# floppy_IDC_to_SMT_rev_A.net
KiCad netlist of a schematic drawn in EAGLE
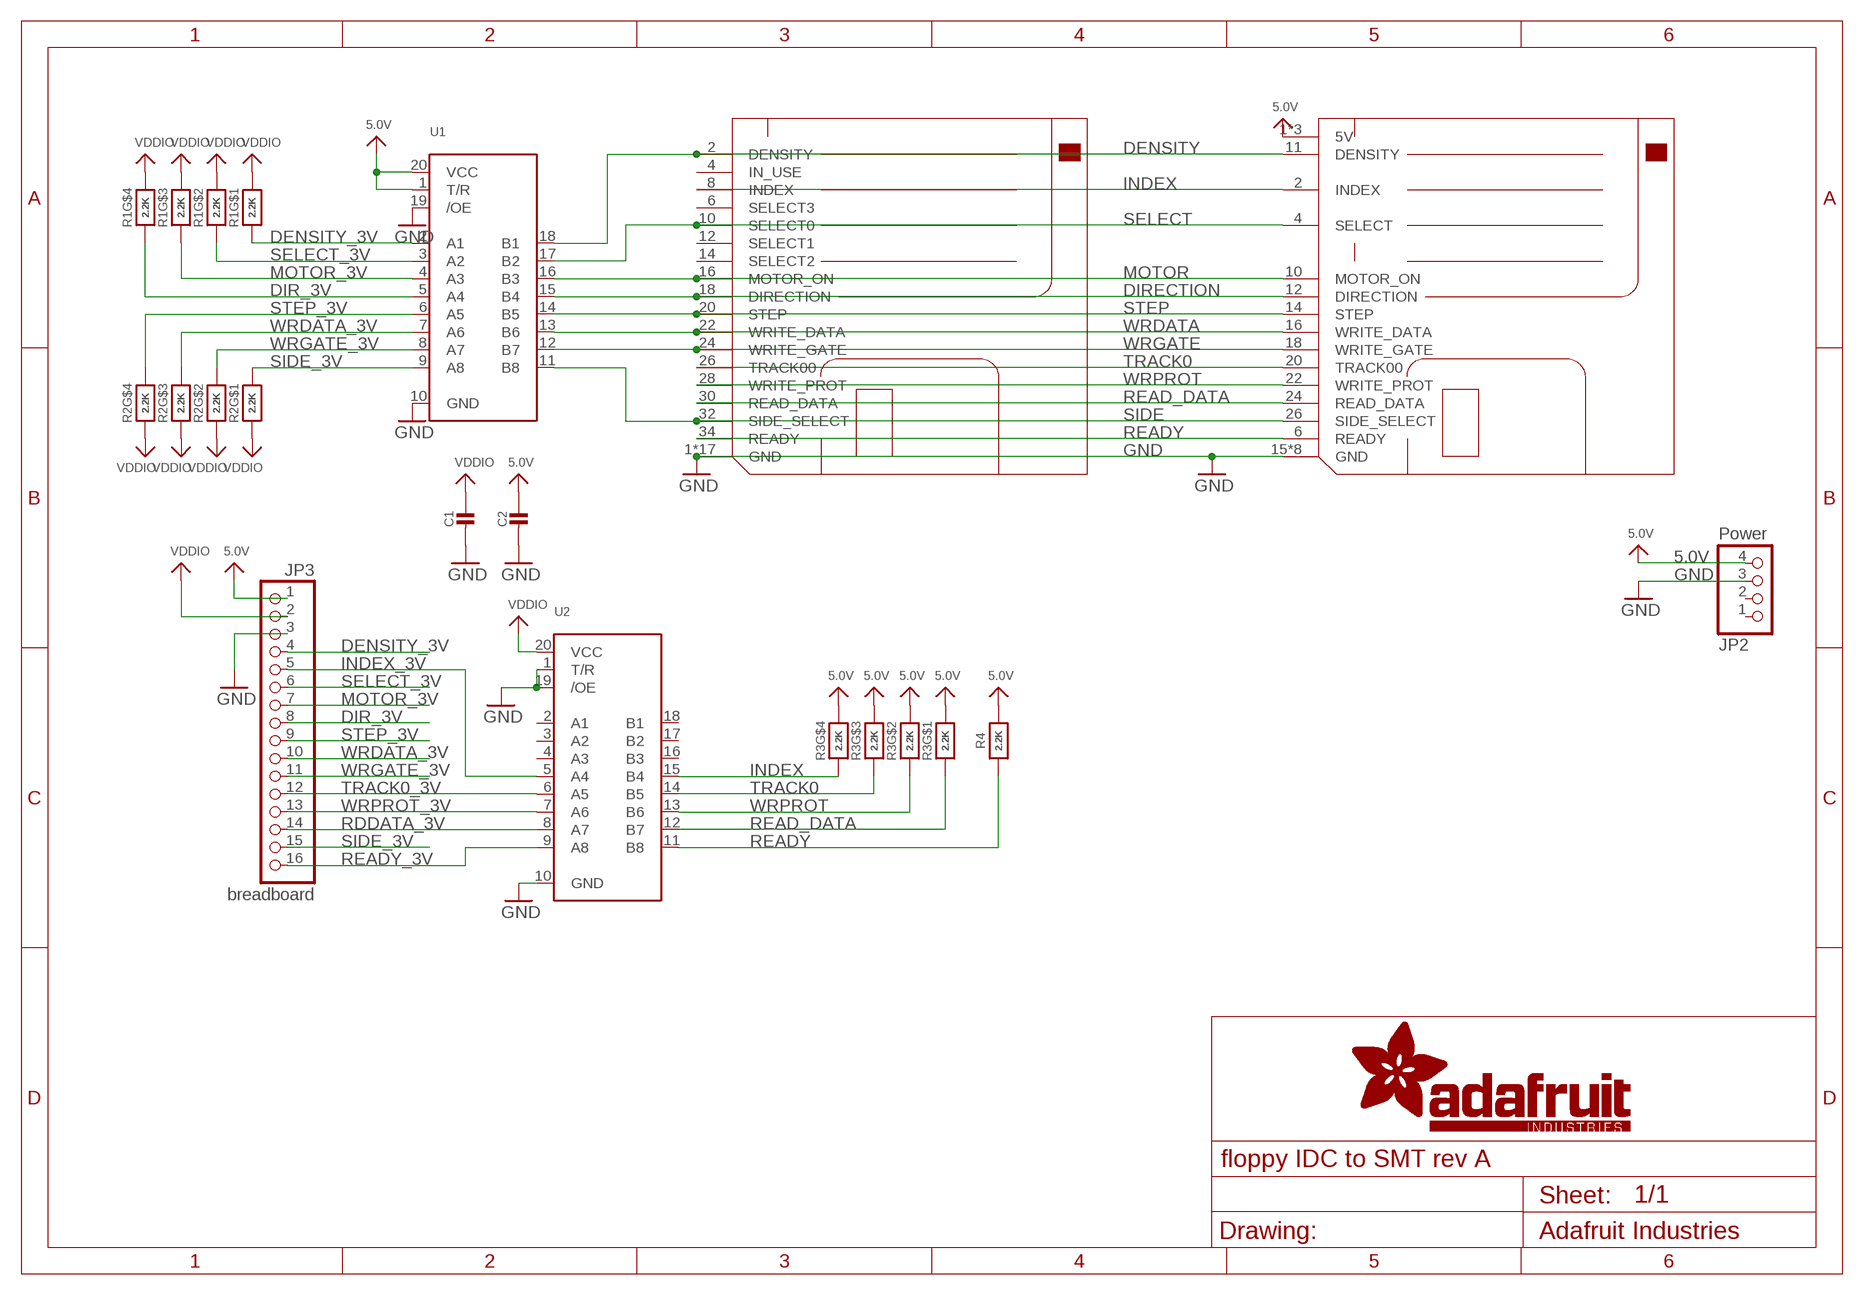
[diagram p0: schematic, sheet 1]

(export (version "E")
  (design (tool "Eeschema 10.0.6"))
  (components
    (comp (ref "C1")
      (value "CAP_CERAMIC0805-NOOUTLINE")
      (footprint "eagle-import:0805-NO")
      (libsource (lib "eagle-import") (part "CAP_CERAMIC0805-NOOUTLINE"))
    )
    (comp (ref "C2")
      (value "CAP_CERAMIC0805-NOOUTLINE")
      (footprint "eagle-import:0805-NO")
      (libsource (lib "eagle-import") (part "CAP_CERAMIC0805-NOOUTLINE"))
    )
    (comp (ref "FDD1")
      (value "FLOPPY_IDC_SHROUDED")
      (footprint "eagle-import:2X17_FLOPPY_IDC")
      (libsource (lib "eagle-import") (part "FLOPPY_IDC_SHROUDED"))
    )
    (comp (ref "FDD2")
      (value "FLOPPY_FPC")
      (footprint "eagle-import:FPC_26P_1MM")
      (libsource (lib "eagle-import") (part "FLOPPY_FPC"))
    )
    (comp (ref "JP2")
      (value "Power")
      (footprint "eagle-import:1X04_90")
      (libsource (lib "eagle-import") (part "PINHD-1X4/90"))
    )
    (comp (ref "JP3")
      (value "breadboard")
      (footprint "eagle-import:1X16")
      (libsource (lib "eagle-import") (part "PINHD-1X16"))
    )
    (comp (ref "R1")
      (value "2.2K")
      (footprint "eagle-import:RESPACK_4X0603")
      (libsource (lib "eagle-import") (part "RESISTOR_4PACK"))
    )
    (comp (ref "R2")
      (value "2.2K")
      (footprint "eagle-import:RESPACK_4X0603")
      (libsource (lib "eagle-import") (part "RESISTOR_4PACK"))
    )
    (comp (ref "R3")
      (value "2.2K")
      (footprint "eagle-import:RESPACK_4X0603")
      (libsource (lib "eagle-import") (part "RESISTOR_4PACK"))
    )
    (comp (ref "R4")
      (value "2.2K")
      (footprint "eagle-import:0603-NO")
      (libsource (lib "eagle-import") (part "RESISTOR_0603_NOOUT"))
    )
    (comp (ref "U1")
      (value "74LCX245")
      (footprint "eagle-import:TSSOP20")
      (libsource (lib "eagle-import") (part "74LCX245"))
    )
    (comp (ref "U2")
      (value "74LCX245")
      (footprint "eagle-import:TSSOP20")
      (libsource (lib "eagle-import") (part "74LCX245"))
    )
  )
  (nets
    (net (code "1") (name "/DENSITY") (class "Default")
      (node (ref "FDD1") (pin "2") (pinfunction "DENSITY_2") (pintype "input"))
      (node (ref "FDD2") (pin "11") (pinfunction "DENSITY_11") (pintype "input"))
      (node (ref "U1") (pin "18") (pinfunction "B1_18") (pintype "bidirectional"))
    )
    (net (code "2") (name "/DENSITY_3V") (class "Default")
      (node (ref "JP3") (pin "4") (pinfunction "4_4") (pintype "passive"))
      (node (ref "R1") (pin "1") (pinfunction "1_1") (pintype "passive"))
      (node (ref "U1") (pin "2") (pinfunction "A1_2") (pintype "bidirectional"))
    )
    (net (code "3") (name "/DIRECTION") (class "Default")
      (node (ref "FDD1") (pin "18") (pinfunction "DIRECTION_18") (pintype "input"))
      (node (ref "FDD2") (pin "12") (pinfunction "DIRECTION_12") (pintype "input"))
      (node (ref "U1") (pin "15") (pinfunction "B4_15") (pintype "bidirectional"))
    )
    (net (code "4") (name "/DIR_3V") (class "Default")
      (node (ref "JP3") (pin "8") (pinfunction "8_8") (pintype "passive"))
      (node (ref "R1") (pin "4") (pinfunction "1_4") (pintype "passive"))
      (node (ref "U1") (pin "5") (pinfunction "A4_5") (pintype "bidirectional"))
    )
    (net (code "5") (name "/INDEX") (class "Default")
      (node (ref "FDD1") (pin "8") (pinfunction "INDEX_8") (pintype "output"))
      (node (ref "FDD2") (pin "2") (pinfunction "INDEX_2") (pintype "output"))
      (node (ref "R3") (pin "4") (pinfunction "1_4") (pintype "passive"))
      (node (ref "U2") (pin "15") (pinfunction "B4_15") (pintype "bidirectional"))
    )
    (net (code "6") (name "/INDEX_3V") (class "Default")
      (node (ref "JP3") (pin "5") (pinfunction "5_5") (pintype "passive"))
      (node (ref "U2") (pin "5") (pinfunction "A4_5") (pintype "bidirectional"))
    )
    (net (code "7") (name "/MOTOR") (class "Default")
      (node (ref "FDD1") (pin "16") (pinfunction "MOTOR_ON_16") (pintype "input"))
      (node (ref "FDD2") (pin "10") (pinfunction "MOTOR_ON_10") (pintype "input"))
      (node (ref "U1") (pin "16") (pinfunction "B3_16") (pintype "bidirectional"))
    )
    (net (code "8") (name "/MOTOR_3V") (class "Default")
      (node (ref "JP3") (pin "7") (pinfunction "7_7") (pintype "passive"))
      (node (ref "R1") (pin "3") (pinfunction "1_3") (pintype "passive"))
      (node (ref "U1") (pin "4") (pinfunction "A3_4") (pintype "bidirectional"))
    )
    (net (code "9") (name "/RDDATA_3V") (class "Default")
      (node (ref "JP3") (pin "14") (pinfunction "14_14") (pintype "passive"))
      (node (ref "U2") (pin "8") (pinfunction "A7_8") (pintype "bidirectional"))
    )
    (net (code "10") (name "/READY") (class "Default")
      (node (ref "FDD1") (pin "34") (pinfunction "READY_34") (pintype "output"))
      (node (ref "FDD2") (pin "6") (pinfunction "READY_6") (pintype "output"))
      (node (ref "R4") (pin "1") (pinfunction "1_1") (pintype "passive"))
      (node (ref "U2") (pin "11") (pinfunction "B8_11") (pintype "bidirectional"))
    )
    (net (code "11") (name "/READY_3V") (class "Default")
      (node (ref "JP3") (pin "16") (pinfunction "16_16") (pintype "passive"))
      (node (ref "U2") (pin "9") (pinfunction "A8_9") (pintype "bidirectional"))
    )
    (net (code "12") (name "/READ_DATA") (class "Default")
      (node (ref "FDD1") (pin "30") (pinfunction "READ_DATA_30") (pintype "output"))
      (node (ref "FDD2") (pin "24") (pinfunction "READ_DATA_24") (pintype "output"))
      (node (ref "R3") (pin "1") (pinfunction "1_1") (pintype "passive"))
      (node (ref "U2") (pin "12") (pinfunction "B7_12") (pintype "bidirectional"))
    )
    (net (code "13") (name "/SELECT") (class "Default")
      (node (ref "FDD1") (pin "10") (pinfunction "SELECT0_10") (pintype "input"))
      (node (ref "FDD2") (pin "4") (pinfunction "SELECT_4") (pintype "input"))
      (node (ref "U1") (pin "17") (pinfunction "B2_17") (pintype "bidirectional"))
    )
    (net (code "14") (name "/SELECT_3V") (class "Default")
      (node (ref "JP3") (pin "6") (pinfunction "6_6") (pintype "passive"))
      (node (ref "R1") (pin "2") (pinfunction "1_2") (pintype "passive"))
      (node (ref "U1") (pin "3") (pinfunction "A2_3") (pintype "bidirectional"))
    )
    (net (code "15") (name "/SIDE") (class "Default")
      (node (ref "FDD1") (pin "32") (pinfunction "SIDE_SELECT_32") (pintype "input"))
      (node (ref "FDD2") (pin "26") (pinfunction "SIDE_SELECT_26") (pintype "input"))
      (node (ref "U1") (pin "11") (pinfunction "B8_11") (pintype "bidirectional"))
    )
    (net (code "16") (name "/SIDE_3V") (class "Default")
      (node (ref "JP3") (pin "15") (pinfunction "15_15") (pintype "passive"))
      (node (ref "R2") (pin "8") (pinfunction "2_8") (pintype "passive"))
      (node (ref "U1") (pin "9") (pinfunction "A8_9") (pintype "bidirectional"))
    )
    (net (code "17") (name "/STEP") (class "Default")
      (node (ref "FDD1") (pin "20") (pinfunction "STEP_20") (pintype "input"))
      (node (ref "FDD2") (pin "14") (pinfunction "STEP_14") (pintype "input"))
      (node (ref "U1") (pin "14") (pinfunction "B5_14") (pintype "bidirectional"))
    )
    (net (code "18") (name "/STEP_3V") (class "Default")
      (node (ref "JP3") (pin "9") (pinfunction "9_9") (pintype "passive"))
      (node (ref "R2") (pin "5") (pinfunction "2_5") (pintype "passive"))
      (node (ref "U1") (pin "6") (pinfunction "A5_6") (pintype "bidirectional"))
    )
    (net (code "19") (name "/TRACK0") (class "Default")
      (node (ref "FDD1") (pin "26") (pinfunction "TRACK00_26") (pintype "output"))
      (node (ref "FDD2") (pin "20") (pinfunction "TRACK00_20") (pintype "output"))
      (node (ref "R3") (pin "3") (pinfunction "1_3") (pintype "passive"))
      (node (ref "U2") (pin "14") (pinfunction "B5_14") (pintype "bidirectional"))
    )
    (net (code "20") (name "/TRACK0_3V") (class "Default")
      (node (ref "JP3") (pin "12") (pinfunction "12_12") (pintype "passive"))
      (node (ref "U2") (pin "6") (pinfunction "A5_6") (pintype "bidirectional"))
    )
    (net (code "21") (name "/WRDATA") (class "Default")
      (node (ref "FDD1") (pin "22") (pinfunction "WRITE_DATA_22") (pintype "input"))
      (node (ref "FDD2") (pin "16") (pinfunction "WRITE_DATA_16") (pintype "input"))
      (node (ref "U1") (pin "13") (pinfunction "B6_13") (pintype "bidirectional"))
    )
    (net (code "22") (name "/WRDATA_3V") (class "Default")
      (node (ref "JP3") (pin "10") (pinfunction "10_10") (pintype "passive"))
      (node (ref "R2") (pin "6") (pinfunction "2_6") (pintype "passive"))
      (node (ref "U1") (pin "7") (pinfunction "A6_7") (pintype "bidirectional"))
    )
    (net (code "23") (name "/WRGATE") (class "Default")
      (node (ref "FDD1") (pin "24") (pinfunction "WRITE_GATE_24") (pintype "input"))
      (node (ref "FDD2") (pin "18") (pinfunction "WRITE_GATE_18") (pintype "input"))
      (node (ref "U1") (pin "12") (pinfunction "B7_12") (pintype "bidirectional"))
    )
    (net (code "24") (name "/WRGATE_3V") (class "Default")
      (node (ref "JP3") (pin "11") (pinfunction "11_11") (pintype "passive"))
      (node (ref "R2") (pin "7") (pinfunction "2_7") (pintype "passive"))
      (node (ref "U1") (pin "8") (pinfunction "A7_8") (pintype "bidirectional"))
    )
    (net (code "25") (name "/WRPROT") (class "Default")
      (node (ref "FDD1") (pin "28") (pinfunction "WRITE_PROT_28") (pintype "output"))
      (node (ref "FDD2") (pin "22") (pinfunction "WRITE_PROT_22") (pintype "output"))
      (node (ref "R3") (pin "2") (pinfunction "1_2") (pintype "passive"))
      (node (ref "U2") (pin "13") (pinfunction "B6_13") (pintype "bidirectional"))
    )
    (net (code "26") (name "/WRPROT_3V") (class "Default")
      (node (ref "JP3") (pin "13") (pinfunction "13_13") (pintype "passive"))
      (node (ref "U2") (pin "7") (pinfunction "A6_7") (pintype "bidirectional"))
    )
    (net (code "27") (name "5.0V") (class "Default")
      (node (ref "C2") (pin "1") (pinfunction "1_1") (pintype "passive"))
      (node (ref "FDD2") (pin "1") (pinfunction "5V_1") (pintype "power_in"))
      (node (ref "FDD2") (pin "3") (pinfunction "5V_3") (pintype "power_in"))
      (node (ref "FDD2") (pin "5") (pinfunction "5V_5") (pintype "power_in"))
      (node (ref "JP2") (pin "4") (pinfunction "4_4") (pintype "passive"))
      (node (ref "JP3") (pin "1") (pinfunction "1_1") (pintype "passive"))
      (node (ref "R3") (pin "5") (pinfunction "2_5") (pintype "passive"))
      (node (ref "R3") (pin "6") (pinfunction "2_6") (pintype "passive"))
      (node (ref "R3") (pin "7") (pinfunction "2_7") (pintype "passive"))
      (node (ref "R3") (pin "8") (pinfunction "2_8") (pintype "passive"))
      (node (ref "R4") (pin "2") (pinfunction "2_2") (pintype "passive"))
      (node (ref "U1") (pin "1") (pinfunction "T/R_1") (pintype "bidirectional"))
      (node (ref "U1") (pin "20") (pinfunction "VCC_20") (pintype "bidirectional"))
    )
    (net (code "28") (name "GND") (class "Default")
      (node (ref "C1") (pin "2") (pinfunction "2_2") (pintype "passive"))
      (node (ref "C2") (pin "2") (pinfunction "2_2") (pintype "passive"))
      (node (ref "FDD1") (pin "1") (pinfunction "GND_1") (pintype "power_in"))
      (node (ref "FDD1") (pin "11") (pinfunction "GND_11") (pintype "power_in"))
      (node (ref "FDD1") (pin "13") (pinfunction "GND_13") (pintype "power_in"))
      (node (ref "FDD1") (pin "15") (pinfunction "GND_15") (pintype "power_in"))
      (node (ref "FDD1") (pin "17") (pinfunction "GND_17") (pintype "power_in"))
      (node (ref "FDD1") (pin "19") (pinfunction "GND_19") (pintype "power_in"))
      (node (ref "FDD1") (pin "21") (pinfunction "GND_21") (pintype "power_in"))
      (node (ref "FDD1") (pin "23") (pinfunction "GND_23") (pintype "power_in"))
      (node (ref "FDD1") (pin "25") (pinfunction "GND_25") (pintype "power_in"))
      (node (ref "FDD1") (pin "27") (pinfunction "GND_27") (pintype "power_in"))
      (node (ref "FDD1") (pin "29") (pinfunction "GND_29") (pintype "power_in"))
      (node (ref "FDD1") (pin "3") (pinfunction "GND_3") (pintype "power_in"))
      (node (ref "FDD1") (pin "31") (pinfunction "GND_31") (pintype "power_in"))
      (node (ref "FDD1") (pin "33") (pinfunction "GND_33") (pintype "power_in"))
      (node (ref "FDD1") (pin "5") (pinfunction "GND_5") (pintype "power_in"))
      (node (ref "FDD1") (pin "7") (pinfunction "GND_7") (pintype "power_in"))
      (node (ref "FDD1") (pin "9") (pinfunction "GND_9") (pintype "power_in"))
      (node (ref "FDD2") (pin "15") (pinfunction "GND_15") (pintype "power_in"))
      (node (ref "FDD2") (pin "17") (pinfunction "GND_17") (pintype "power_in"))
      (node (ref "FDD2") (pin "19") (pinfunction "GND_19") (pintype "power_in"))
      (node (ref "FDD2") (pin "21") (pinfunction "GND_21") (pintype "power_in"))
      (node (ref "FDD2") (pin "23") (pinfunction "GND_23") (pintype "power_in"))
      (node (ref "FDD2") (pin "25") (pinfunction "GND_25") (pintype "power_in"))
      (node (ref "FDD2") (pin "M1") (pinfunction "GND_M1") (pintype "power_in"))
      (node (ref "FDD2") (pin "M2") (pinfunction "GND_M2") (pintype "power_in"))
      (node (ref "JP2") (pin "3") (pinfunction "3_3") (pintype "passive"))
      (node (ref "JP3") (pin "3") (pinfunction "3_3") (pintype "passive"))
      (node (ref "U1") (pin "10") (pinfunction "GND_10") (pintype "bidirectional"))
      (node (ref "U1") (pin "19") (pinfunction "/OE_19") (pintype "bidirectional"))
      (node (ref "U2") (pin "1") (pinfunction "T/R_1") (pintype "bidirectional"))
      (node (ref "U2") (pin "10") (pinfunction "GND_10") (pintype "bidirectional"))
      (node (ref "U2") (pin "19") (pinfunction "/OE_19") (pintype "bidirectional"))
    )
    (net (code "29") (name "VDDIO") (class "Default")
      (node (ref "C1") (pin "1") (pinfunction "1_1") (pintype "passive"))
      (node (ref "JP3") (pin "2") (pinfunction "2_2") (pintype "passive"))
      (node (ref "R1") (pin "5") (pinfunction "2_5") (pintype "passive"))
      (node (ref "R1") (pin "6") (pinfunction "2_6") (pintype "passive"))
      (node (ref "R1") (pin "7") (pinfunction "2_7") (pintype "passive"))
      (node (ref "R1") (pin "8") (pinfunction "2_8") (pintype "passive"))
      (node (ref "R2") (pin "1") (pinfunction "1_1") (pintype "passive"))
      (node (ref "R2") (pin "2") (pinfunction "1_2") (pintype "passive"))
      (node (ref "R2") (pin "3") (pinfunction "1_3") (pintype "passive"))
      (node (ref "R2") (pin "4") (pinfunction "1_4") (pintype "passive"))
      (node (ref "U2") (pin "20") (pinfunction "VCC_20") (pintype "bidirectional"))
    )
    (net (code "30") (name "unconnected-(FDD1-IN_USE-Pad4)") (class "Default")
      (node (ref "FDD1") (pin "4") (pinfunction "IN_USE_4") (pintype "input"))
    )
    (net (code "31") (name "unconnected-(FDD1-SELECT1-Pad12)") (class "Default")
      (node (ref "FDD1") (pin "12") (pinfunction "SELECT1_12") (pintype "input"))
    )
    (net (code "32") (name "unconnected-(FDD1-SELECT2-Pad14)") (class "Default")
      (node (ref "FDD1") (pin "14") (pinfunction "SELECT2_14") (pintype "input"))
    )
    (net (code "33") (name "unconnected-(FDD1-SELECT3-Pad6)") (class "Default")
      (node (ref "FDD1") (pin "6") (pinfunction "SELECT3_6") (pintype "input"))
    )
    (net (code "34") (name "unconnected-(JP2-Pad1)") (class "Default")
      (node (ref "JP2") (pin "1") (pinfunction "1_1") (pintype "passive"))
    )
    (net (code "35") (name "unconnected-(JP2-Pad2)") (class "Default")
      (node (ref "JP2") (pin "2") (pinfunction "2_2") (pintype "passive"))
    )
    (net (code "36") (name "unconnected-(U2-A1-Pad2)") (class "Default")
      (node (ref "U2") (pin "2") (pinfunction "A1_2") (pintype "bidirectional"))
    )
    (net (code "37") (name "unconnected-(U2-A2-Pad3)") (class "Default")
      (node (ref "U2") (pin "3") (pinfunction "A2_3") (pintype "bidirectional"))
    )
    (net (code "38") (name "unconnected-(U2-A3-Pad4)") (class "Default")
      (node (ref "U2") (pin "4") (pinfunction "A3_4") (pintype "bidirectional"))
    )
    (net (code "39") (name "unconnected-(U2-B1-Pad18)") (class "Default")
      (node (ref "U2") (pin "18") (pinfunction "B1_18") (pintype "bidirectional"))
    )
    (net (code "40") (name "unconnected-(U2-B2-Pad17)") (class "Default")
      (node (ref "U2") (pin "17") (pinfunction "B2_17") (pintype "bidirectional"))
    )
    (net (code "41") (name "unconnected-(U2-B3-Pad16)") (class "Default")
      (node (ref "U2") (pin "16") (pinfunction "B3_16") (pintype "bidirectional"))
    )
  )
)
